# volume_board_v3.net
KiCad netlist of a schematic drawn in EAGLE
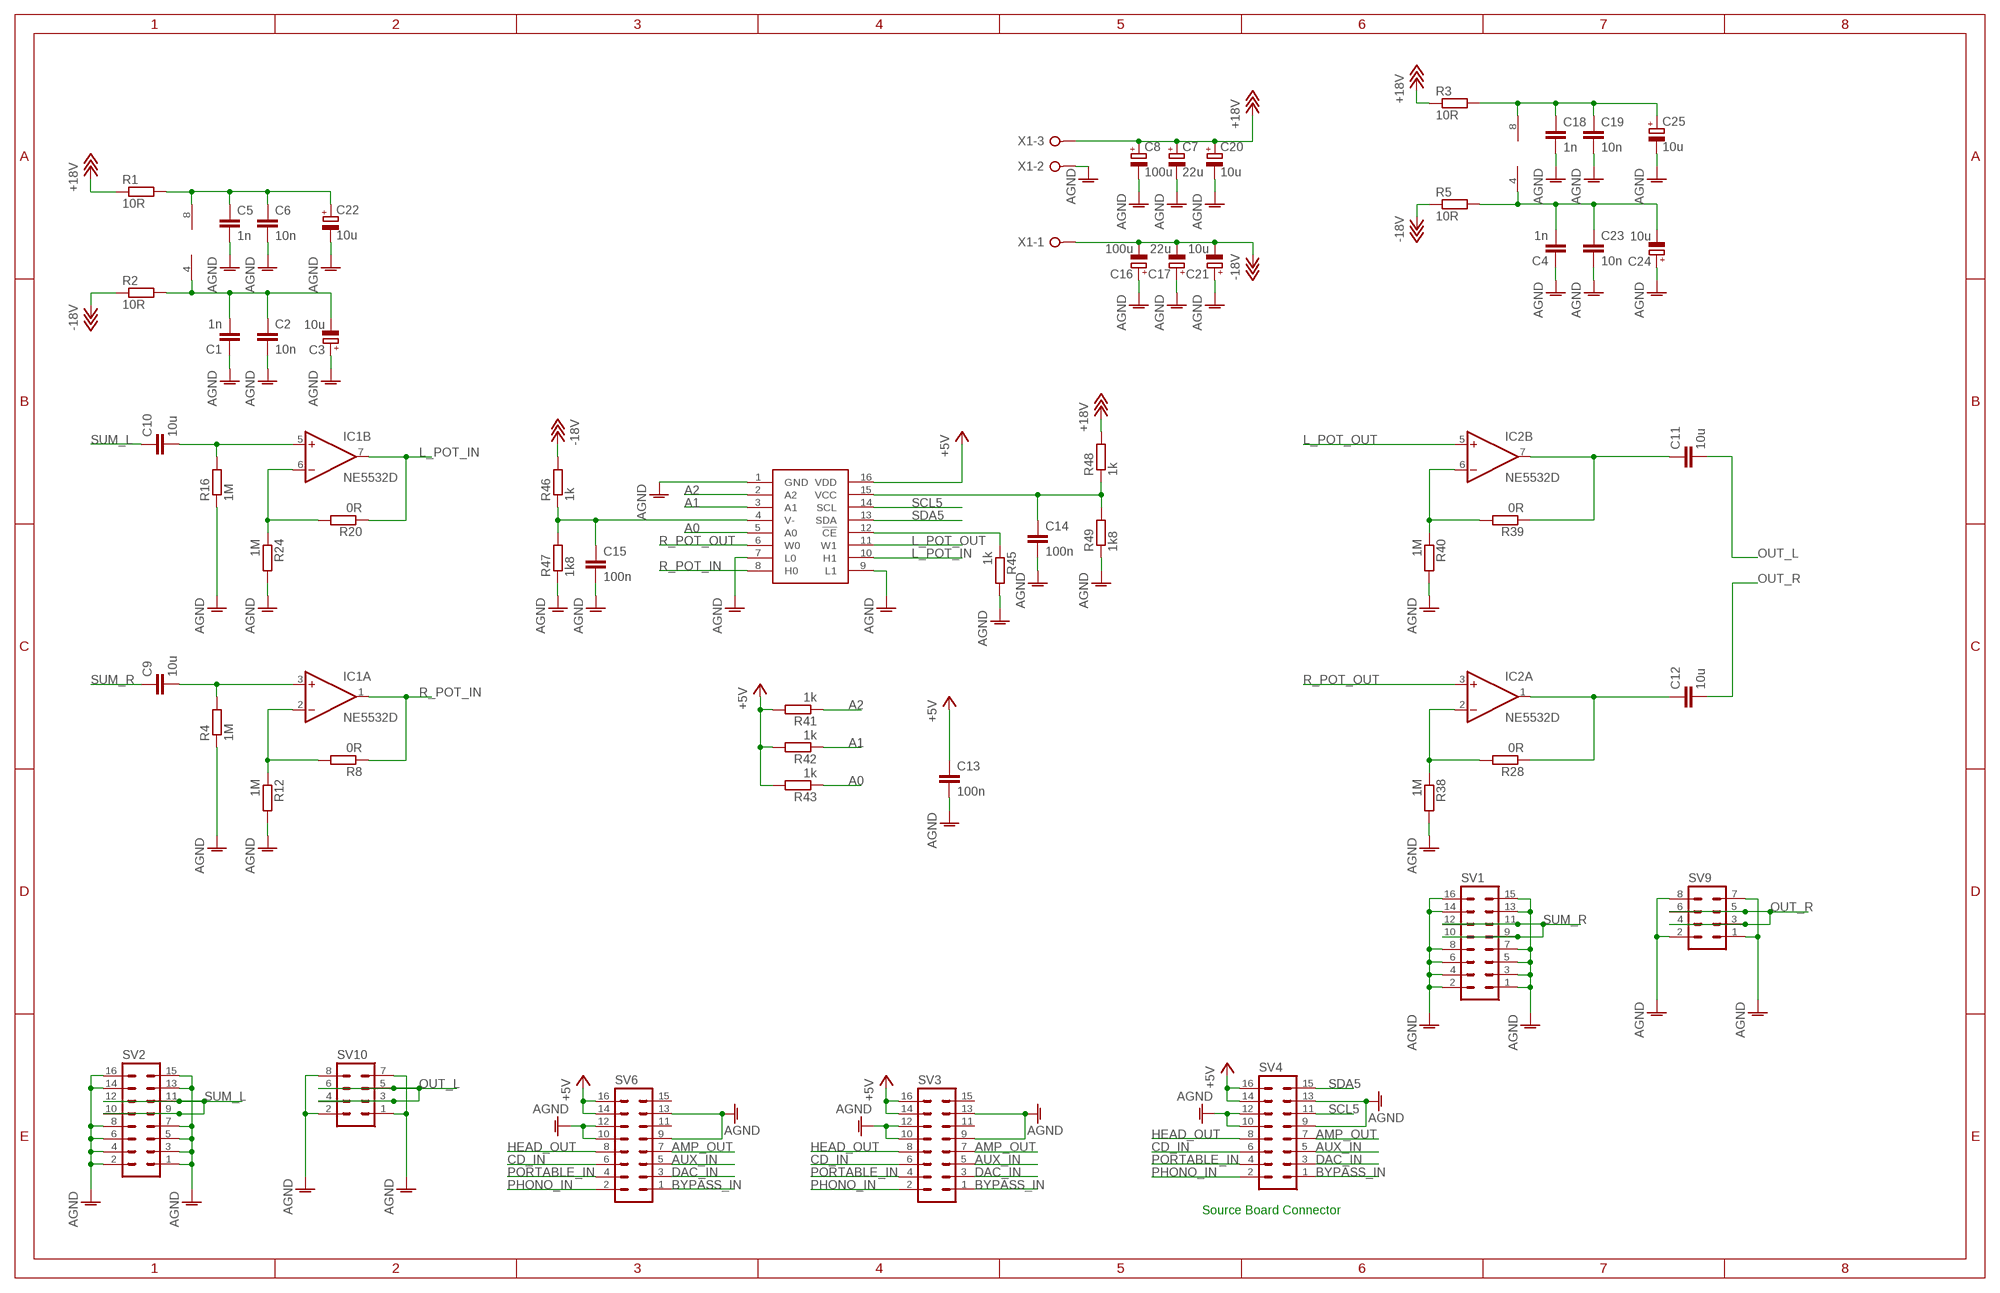
[diagram p0: schematic, sheet 1]

(export (version "E")
  (design (tool "Eeschema 10.0.6"))
  (components
    (comp (ref "C1")
      (value "1n")
      (footprint "eagle-import:C0603")
      (libsource (lib "eagle-import") (part "C-EUC0603"))
    )
    (comp (ref "C2")
      (value "10n")
      (footprint "eagle-import:C0603")
      (libsource (lib "eagle-import") (part "C-EUC0603"))
    )
    (comp (ref "C3")
      (value "10u")
      (footprint "eagle-import:153CLV-0405")
      (libsource (lib "eagle-import") (part "CPOL-EU153CLV-0405"))
    )
    (comp (ref "C4")
      (value "1n")
      (footprint "eagle-import:C0603")
      (libsource (lib "eagle-import") (part "C-EUC0603"))
    )
    (comp (ref "C5")
      (value "1n")
      (footprint "eagle-import:C0603")
      (libsource (lib "eagle-import") (part "C-EUC0603"))
    )
    (comp (ref "C6")
      (value "10n")
      (footprint "eagle-import:C0603")
      (libsource (lib "eagle-import") (part "C-EUC0603"))
    )
    (comp (ref "C7")
      (value "22u")
      (footprint "eagle-import:153CLV-0405")
      (libsource (lib "eagle-import") (part "CPOL-EU153CLV-0405"))
    )
    (comp (ref "C8")
      (value "100u")
      (footprint "eagle-import:153CLV-0605")
      (libsource (lib "eagle-import") (part "CPOL-EU153CLV-0605"))
    )
    (comp (ref "C9")
      (value "10u")
      (footprint "eagle-import:C5B7.2_11")
      (libsource (lib "eagle-import") (part "C5/7.2/11"))
    )
    (comp (ref "C10")
      (value "10u")
      (footprint "eagle-import:C5B7.2_11")
      (libsource (lib "eagle-import") (part "C5/7.2/11"))
    )
    (comp (ref "C11")
      (value "10u")
      (footprint "eagle-import:C5B7.2_11")
      (libsource (lib "eagle-import") (part "C5/7.2/11"))
    )
    (comp (ref "C12")
      (value "10u")
      (footprint "eagle-import:C5B7.2_11")
      (libsource (lib "eagle-import") (part "C5/7.2/11"))
    )
    (comp (ref "C13")
      (value "100n")
      (footprint "eagle-import:C0603")
      (libsource (lib "eagle-import") (part "C-EUC0603"))
    )
    (comp (ref "C14")
      (value "100n")
      (footprint "eagle-import:C0603")
      (libsource (lib "eagle-import") (part "C-EUC0603"))
    )
    (comp (ref "C15")
      (value "100n")
      (footprint "eagle-import:C0603")
      (libsource (lib "eagle-import") (part "C-EUC0603"))
    )
    (comp (ref "C16")
      (value "100u")
      (footprint "eagle-import:153CLV-0605")
      (libsource (lib "eagle-import") (part "CPOL-EU153CLV-0605"))
    )
    (comp (ref "C17")
      (value "22u")
      (footprint "eagle-import:153CLV-0405")
      (libsource (lib "eagle-import") (part "CPOL-EU153CLV-0405"))
    )
    (comp (ref "C18")
      (value "1n")
      (footprint "eagle-import:C0603")
      (libsource (lib "eagle-import") (part "C-EUC0603"))
    )
    (comp (ref "C19")
      (value "10n")
      (footprint "eagle-import:C0603")
      (libsource (lib "eagle-import") (part "C-EUC0603"))
    )
    (comp (ref "C20")
      (value "10u")
      (footprint "eagle-import:153CLV-0405")
      (libsource (lib "eagle-import") (part "CPOL-EU153CLV-0405"))
    )
    (comp (ref "C21")
      (value "10u")
      (footprint "eagle-import:153CLV-0405")
      (libsource (lib "eagle-import") (part "CPOL-EU153CLV-0405"))
    )
    (comp (ref "C22")
      (value "10u")
      (footprint "eagle-import:153CLV-0405")
      (libsource (lib "eagle-import") (part "CPOL-EU153CLV-0405"))
    )
    (comp (ref "C23")
      (value "10n")
      (footprint "eagle-import:C0603")
      (libsource (lib "eagle-import") (part "C-EUC0603"))
    )
    (comp (ref "C24")
      (value "10u")
      (footprint "eagle-import:153CLV-0405")
      (libsource (lib "eagle-import") (part "CPOL-EU153CLV-0405"))
    )
    (comp (ref "C25")
      (value "10u")
      (footprint "eagle-import:153CLV-0405")
      (libsource (lib "eagle-import") (part "CPOL-EU153CLV-0405"))
    )
    (comp (ref "IC1")
      (value "NE5532D")
      (footprint "eagle-import:SO08")
      (libsource (lib "eagle-import") (part "NE5532D"))
    )
    (comp (ref "IC2")
      (value "NE5532D")
      (footprint "eagle-import:SO08")
      (libsource (lib "eagle-import") (part "NE5532D"))
    )
    (comp (ref "IC4")
      (value "DS1882")
      (footprint "eagle-import:SO16")
      (libsource (lib "eagle-import") (part "DS1882"))
    )
    (comp (ref "R1")
      (value "10R")
      (footprint "eagle-import:R0603")
      (libsource (lib "eagle-import") (part "R-EU_R0603"))
    )
    (comp (ref "R2")
      (value "10R")
      (footprint "eagle-import:R0603")
      (libsource (lib "eagle-import") (part "R-EU_R0603"))
    )
    (comp (ref "R3")
      (value "10R")
      (footprint "eagle-import:R0603")
      (libsource (lib "eagle-import") (part "R-EU_R0603"))
    )
    (comp (ref "R4")
      (value "1M")
      (footprint "eagle-import:R0603")
      (libsource (lib "eagle-import") (part "resistor_R-EU_R0603"))
    )
    (comp (ref "R5")
      (value "10R")
      (footprint "eagle-import:R0603")
      (libsource (lib "eagle-import") (part "R-EU_R0603"))
    )
    (comp (ref "R8")
      (value "0R")
      (footprint "eagle-import:R0603")
      (libsource (lib "eagle-import") (part "resistor_R-EU_R0603"))
    )
    (comp (ref "R12")
      (value "1M")
      (footprint "eagle-import:R0603")
      (libsource (lib "eagle-import") (part "resistor_R-EU_R0603"))
    )
    (comp (ref "R16")
      (value "1M")
      (footprint "eagle-import:R0603")
      (libsource (lib "eagle-import") (part "resistor_R-EU_R0603"))
    )
    (comp (ref "R20")
      (value "0R")
      (footprint "eagle-import:R0603")
      (libsource (lib "eagle-import") (part "resistor_R-EU_R0603"))
    )
    (comp (ref "R24")
      (value "1M")
      (footprint "eagle-import:R0603")
      (libsource (lib "eagle-import") (part "resistor_R-EU_R0603"))
    )
    (comp (ref "R28")
      (value "0R")
      (footprint "eagle-import:R0603")
      (libsource (lib "eagle-import") (part "resistor_R-EU_R0603"))
    )
    (comp (ref "R38")
      (value "1M")
      (footprint "eagle-import:R0603")
      (libsource (lib "eagle-import") (part "resistor_R-EU_R0603"))
    )
    (comp (ref "R39")
      (value "0R")
      (footprint "eagle-import:R0603")
      (libsource (lib "eagle-import") (part "resistor_R-EU_R0603"))
    )
    (comp (ref "R40")
      (value "1M")
      (footprint "eagle-import:R0603")
      (libsource (lib "eagle-import") (part "resistor_R-EU_R0603"))
    )
    (comp (ref "R41")
      (value "1k")
      (footprint "eagle-import:R0603")
      (libsource (lib "eagle-import") (part "resistor_R-EU_R0603"))
    )
    (comp (ref "R42")
      (value "1k")
      (footprint "eagle-import:R0603")
      (libsource (lib "eagle-import") (part "resistor_R-EU_R0603"))
    )
    (comp (ref "R43")
      (value "1k")
      (footprint "eagle-import:R0603")
      (libsource (lib "eagle-import") (part "resistor_R-EU_R0603"))
    )
    (comp (ref "R45")
      (value "1k")
      (footprint "eagle-import:R0603")
      (libsource (lib "eagle-import") (part "resistor_R-EU_R0603"))
    )
    (comp (ref "R46")
      (value "1k")
      (footprint "eagle-import:R0603")
      (libsource (lib "eagle-import") (part "resistor_R-EU_R0603"))
    )
    (comp (ref "R47")
      (value "1k8")
      (footprint "eagle-import:R0603")
      (libsource (lib "eagle-import") (part "resistor_R-EU_R0603"))
    )
    (comp (ref "R48")
      (value "1k")
      (footprint "eagle-import:R0603")
      (libsource (lib "eagle-import") (part "resistor_R-EU_R0603"))
    )
    (comp (ref "R49")
      (value "1k8")
      (footprint "eagle-import:R0603")
      (libsource (lib "eagle-import") (part "resistor_R-EU_R0603"))
    )
    (comp (ref "SV1")
      (value "MA08-2")
      (footprint "eagle-import:MA08-2")
      (libsource (lib "eagle-import") (part "MA08-2"))
    )
    (comp (ref "SV2")
      (value "MA08-2")
      (footprint "eagle-import:MA08-2")
      (libsource (lib "eagle-import") (part "MA08-2"))
    )
    (comp (ref "SV3")
      (value "MA08-2")
      (footprint "eagle-import:MA08-2")
      (libsource (lib "eagle-import") (part "MA08-2"))
    )
    (comp (ref "SV4")
      (value "MA08-2B")
      (footprint "eagle-import:MA08-2_BORDER")
      (libsource (lib "eagle-import") (part "MA08-2B"))
    )
    (comp (ref "SV6")
      (value "MA08-2")
      (footprint "eagle-import:MA08-2")
      (libsource (lib "eagle-import") (part "MA08-2"))
    )
    (comp (ref "SV9")
      (value "MA04-2")
      (footprint "eagle-import:MA04-2")
      (libsource (lib "eagle-import") (part "MA04-2"))
    )
    (comp (ref "SV10")
      (value "MA04-2")
      (footprint "eagle-import:MA04-2")
      (libsource (lib "eagle-import") (part "MA04-2"))
    )
    (comp (ref "X1")
      (value "W237-3E")
      (footprint "eagle-import:W237-3E")
      (libsource (lib "eagle-import") (part "W237-3E"))
    )
  )
  (nets
    (net (code "1") (name "+5V") (class "Default")
      (node (ref "C13") (pin "1") (pinfunction "1_1") (pintype "passive"))
      (node (ref "IC4") (pin "16") (pinfunction "VDD_16") (pintype "power_in"))
      (node (ref "R41") (pin "2") (pinfunction "2_2") (pintype "passive"))
      (node (ref "R42") (pin "2") (pinfunction "2_2") (pintype "passive"))
      (node (ref "R43") (pin "2") (pinfunction "2_2") (pintype "passive"))
      (node (ref "SV3") (pin "14") (pinfunction "14_14") (pintype "passive"))
      (node (ref "SV3") (pin "16") (pinfunction "16_16") (pintype "passive"))
      (node (ref "SV4") (pin "14") (pinfunction "14_14") (pintype "passive"))
      (node (ref "SV4") (pin "16") (pinfunction "16_16") (pintype "passive"))
      (node (ref "SV6") (pin "14") (pinfunction "14_14") (pintype "passive"))
      (node (ref "SV6") (pin "16") (pinfunction "16_16") (pintype "passive"))
    )
    (net (code "2") (name "+18V") (class "Default")
      (node (ref "C20") (pin "+") (pinfunction "+_+") (pintype "passive"))
      (node (ref "C7") (pin "+") (pinfunction "+_+") (pintype "passive"))
      (node (ref "C8") (pin "+") (pinfunction "+_+") (pintype "passive"))
      (node (ref "R1") (pin "1") (pinfunction "1_1") (pintype "passive"))
      (node (ref "R3") (pin "1") (pinfunction "1_1") (pintype "passive"))
      (node (ref "R48") (pin "2") (pinfunction "2_2") (pintype "passive"))
      (node (ref "X1") (pin "3") (pinfunction "KL_3") (pintype "passive"))
    )
    (net (code "3") (name "-18V") (class "Default")
      (node (ref "C16") (pin "-") (pinfunction "-_-") (pintype "passive"))
      (node (ref "C17") (pin "-") (pinfunction "-_-") (pintype "passive"))
      (node (ref "C21") (pin "-") (pinfunction "-_-") (pintype "passive"))
      (node (ref "R2") (pin "1") (pinfunction "1_1") (pintype "passive"))
      (node (ref "R46") (pin "2") (pinfunction "2_2") (pintype "passive"))
      (node (ref "R5") (pin "1") (pinfunction "1_1") (pintype "passive"))
      (node (ref "X1") (pin "1") (pinfunction "KL_1") (pintype "passive"))
    )
    (net (code "4") (name "/A0") (class "Default")
      (node (ref "IC4") (pin "5") (pinfunction "A0_5") (pintype "bidirectional"))
      (node (ref "R43") (pin "1") (pinfunction "1_1") (pintype "passive"))
    )
    (net (code "5") (name "/A1") (class "Default")
      (node (ref "IC4") (pin "3") (pinfunction "A1_3") (pintype "bidirectional"))
      (node (ref "R42") (pin "1") (pinfunction "1_1") (pintype "passive"))
    )
    (net (code "6") (name "/A2") (class "Default")
      (node (ref "IC4") (pin "2") (pinfunction "A2_2") (pintype "bidirectional"))
      (node (ref "R41") (pin "1") (pinfunction "1_1") (pintype "passive"))
    )
    (net (code "7") (name "/AMP_OUT") (class "Default")
      (node (ref "SV3") (pin "7") (pinfunction "7_7") (pintype "passive"))
      (node (ref "SV4") (pin "7") (pinfunction "7_7") (pintype "passive"))
      (node (ref "SV6") (pin "7") (pinfunction "7_7") (pintype "passive"))
    )
    (net (code "8") (name "/AUX_IN") (class "Default")
      (node (ref "SV3") (pin "5") (pinfunction "5_5") (pintype "passive"))
      (node (ref "SV4") (pin "5") (pinfunction "5_5") (pintype "passive"))
      (node (ref "SV6") (pin "5") (pinfunction "5_5") (pintype "passive"))
    )
    (net (code "9") (name "/BYPASS_IN") (class "Default")
      (node (ref "SV3") (pin "1") (pinfunction "1_1") (pintype "passive"))
      (node (ref "SV4") (pin "1") (pinfunction "1_1") (pintype "passive"))
      (node (ref "SV6") (pin "1") (pinfunction "1_1") (pintype "passive"))
    )
    (net (code "10") (name "/CD_IN") (class "Default")
      (node (ref "SV3") (pin "6") (pinfunction "6_6") (pintype "passive"))
      (node (ref "SV4") (pin "6") (pinfunction "6_6") (pintype "passive"))
      (node (ref "SV6") (pin "6") (pinfunction "6_6") (pintype "passive"))
    )
    (net (code "11") (name "/DAC_IN") (class "Default")
      (node (ref "SV3") (pin "3") (pinfunction "3_3") (pintype "passive"))
      (node (ref "SV4") (pin "3") (pinfunction "3_3") (pintype "passive"))
      (node (ref "SV6") (pin "3") (pinfunction "3_3") (pintype "passive"))
    )
    (net (code "12") (name "/HEAD_OUT") (class "Default")
      (node (ref "SV3") (pin "8") (pinfunction "8_8") (pintype "passive"))
      (node (ref "SV4") (pin "8") (pinfunction "8_8") (pintype "passive"))
      (node (ref "SV6") (pin "8") (pinfunction "8_8") (pintype "passive"))
    )
    (net (code "13") (name "/L_POT_IN") (class "Default")
      (node (ref "IC1") (pin "7") (pinfunction "OUT_7") (pintype "output"))
      (node (ref "IC4") (pin "10") (pinfunction "H1_10") (pintype "bidirectional"))
      (node (ref "R20") (pin "1") (pinfunction "1_1") (pintype "passive"))
    )
    (net (code "14") (name "/L_POT_OUT") (class "Default")
      (node (ref "IC2") (pin "5") (pinfunction "+IN_5") (pintype "input"))
      (node (ref "IC4") (pin "11") (pinfunction "W1_11") (pintype "bidirectional"))
    )
    (net (code "15") (name "/OUT_L") (class "Default")
      (node (ref "C11") (pin "2") (pinfunction "2_2") (pintype "passive"))
      (node (ref "SV10") (pin "3") (pinfunction "3_3") (pintype "passive"))
      (node (ref "SV10") (pin "4") (pinfunction "4_4") (pintype "passive"))
      (node (ref "SV10") (pin "5") (pinfunction "5_5") (pintype "passive"))
      (node (ref "SV10") (pin "6") (pinfunction "6_6") (pintype "passive"))
    )
    (net (code "16") (name "/OUT_R") (class "Default")
      (node (ref "C12") (pin "2") (pinfunction "2_2") (pintype "passive"))
      (node (ref "SV9") (pin "3") (pinfunction "3_3") (pintype "passive"))
      (node (ref "SV9") (pin "4") (pinfunction "4_4") (pintype "passive"))
      (node (ref "SV9") (pin "5") (pinfunction "5_5") (pintype "passive"))
      (node (ref "SV9") (pin "6") (pinfunction "6_6") (pintype "passive"))
    )
    (net (code "17") (name "/PHONO_IN") (class "Default")
      (node (ref "SV3") (pin "2") (pinfunction "2_2") (pintype "passive"))
      (node (ref "SV4") (pin "2") (pinfunction "2_2") (pintype "passive"))
      (node (ref "SV6") (pin "2") (pinfunction "2_2") (pintype "passive"))
    )
    (net (code "18") (name "/PORTABLE_IN") (class "Default")
      (node (ref "SV3") (pin "4") (pinfunction "4_4") (pintype "passive"))
      (node (ref "SV4") (pin "4") (pinfunction "4_4") (pintype "passive"))
      (node (ref "SV6") (pin "4") (pinfunction "4_4") (pintype "passive"))
    )
    (net (code "19") (name "/R_POT_IN") (class "Default")
      (node (ref "IC1") (pin "1") (pinfunction "OUT_1") (pintype "output"))
      (node (ref "IC4") (pin "8") (pinfunction "H0_8") (pintype "bidirectional"))
      (node (ref "R8") (pin "1") (pinfunction "1_1") (pintype "passive"))
    )
    (net (code "20") (name "/R_POT_OUT") (class "Default")
      (node (ref "IC2") (pin "3") (pinfunction "+IN_3") (pintype "input"))
      (node (ref "IC4") (pin "6") (pinfunction "W0_6") (pintype "bidirectional"))
    )
    (net (code "21") (name "/SCL5") (class "Default")
      (node (ref "IC4") (pin "14") (pinfunction "SCL_14") (pintype "bidirectional"))
      (node (ref "SV4") (pin "11") (pinfunction "11_11") (pintype "passive"))
    )
    (net (code "22") (name "/SDA5") (class "Default")
      (node (ref "IC4") (pin "13") (pinfunction "SDA_13") (pintype "bidirectional"))
      (node (ref "SV4") (pin "15") (pinfunction "15_15") (pintype "passive"))
    )
    (net (code "23") (name "/SUM_L") (class "Default")
      (node (ref "C10") (pin "1") (pinfunction "1_1") (pintype "passive"))
      (node (ref "SV2") (pin "10") (pinfunction "10_10") (pintype "passive"))
      (node (ref "SV2") (pin "11") (pinfunction "11_11") (pintype "passive"))
      (node (ref "SV2") (pin "12") (pinfunction "12_12") (pintype "passive"))
      (node (ref "SV2") (pin "9") (pinfunction "9_9") (pintype "passive"))
    )
    (net (code "24") (name "/SUM_R") (class "Default")
      (node (ref "C9") (pin "1") (pinfunction "1_1") (pintype "passive"))
      (node (ref "SV1") (pin "10") (pinfunction "10_10") (pintype "passive"))
      (node (ref "SV1") (pin "11") (pinfunction "11_11") (pintype "passive"))
      (node (ref "SV1") (pin "12") (pinfunction "12_12") (pintype "passive"))
      (node (ref "SV1") (pin "9") (pinfunction "9_9") (pintype "passive"))
    )
    (net (code "25") (name "AGND") (class "Default")
      (node (ref "C1") (pin "1") (pinfunction "1_1") (pintype "passive"))
      (node (ref "C13") (pin "2") (pinfunction "2_2") (pintype "passive"))
      (node (ref "C14") (pin "2") (pinfunction "2_2") (pintype "passive"))
      (node (ref "C15") (pin "2") (pinfunction "2_2") (pintype "passive"))
      (node (ref "C16") (pin "+") (pinfunction "+_+") (pintype "passive"))
      (node (ref "C17") (pin "+") (pinfunction "+_+") (pintype "passive"))
      (node (ref "C18") (pin "2") (pinfunction "2_2") (pintype "passive"))
      (node (ref "C19") (pin "2") (pinfunction "2_2") (pintype "passive"))
      (node (ref "C2") (pin "2") (pinfunction "2_2") (pintype "passive"))
      (node (ref "C20") (pin "-") (pinfunction "-_-") (pintype "passive"))
      (node (ref "C21") (pin "+") (pinfunction "+_+") (pintype "passive"))
      (node (ref "C22") (pin "-") (pinfunction "-_-") (pintype "passive"))
      (node (ref "C23") (pin "2") (pinfunction "2_2") (pintype "passive"))
      (node (ref "C24") (pin "+") (pinfunction "+_+") (pintype "passive"))
      (node (ref "C25") (pin "-") (pinfunction "-_-") (pintype "passive"))
      (node (ref "C3") (pin "+") (pinfunction "+_+") (pintype "passive"))
      (node (ref "C4") (pin "1") (pinfunction "1_1") (pintype "passive"))
      (node (ref "C5") (pin "2") (pinfunction "2_2") (pintype "passive"))
      (node (ref "C6") (pin "2") (pinfunction "2_2") (pintype "passive"))
      (node (ref "C7") (pin "-") (pinfunction "-_-") (pintype "passive"))
      (node (ref "C8") (pin "-") (pinfunction "-_-") (pintype "passive"))
      (node (ref "IC4") (pin "1") (pinfunction "GND_1") (pintype "power_in"))
      (node (ref "IC4") (pin "7") (pinfunction "L0_7") (pintype "bidirectional"))
      (node (ref "IC4") (pin "9") (pinfunction "L1_9") (pintype "bidirectional"))
      (node (ref "R12") (pin "2") (pinfunction "2_2") (pintype "passive"))
      (node (ref "R16") (pin "1") (pinfunction "1_1") (pintype "passive"))
      (node (ref "R24") (pin "2") (pinfunction "2_2") (pintype "passive"))
      (node (ref "R38") (pin "2") (pinfunction "2_2") (pintype "passive"))
      (node (ref "R4") (pin "1") (pinfunction "1_1") (pintype "passive"))
      (node (ref "R40") (pin "2") (pinfunction "2_2") (pintype "passive"))
      (node (ref "R45") (pin "2") (pinfunction "2_2") (pintype "passive"))
      (node (ref "R47") (pin "1") (pinfunction "1_1") (pintype "passive"))
      (node (ref "R49") (pin "1") (pinfunction "1_1") (pintype "passive"))
      (node (ref "SV1") (pin "1") (pinfunction "1_1") (pintype "passive"))
      (node (ref "SV1") (pin "13") (pinfunction "13_13") (pintype "passive"))
      (node (ref "SV1") (pin "14") (pinfunction "14_14") (pintype "passive"))
      (node (ref "SV1") (pin "15") (pinfunction "15_15") (pintype "passive"))
      (node (ref "SV1") (pin "16") (pinfunction "16_16") (pintype "passive"))
      (node (ref "SV1") (pin "2") (pinfunction "2_2") (pintype "passive"))
      (node (ref "SV1") (pin "3") (pinfunction "3_3") (pintype "passive"))
      (node (ref "SV1") (pin "4") (pinfunction "4_4") (pintype "passive"))
      (node (ref "SV1") (pin "5") (pinfunction "5_5") (pintype "passive"))
      (node (ref "SV1") (pin "6") (pinfunction "6_6") (pintype "passive"))
      (node (ref "SV1") (pin "7") (pinfunction "7_7") (pintype "passive"))
      (node (ref "SV1") (pin "8") (pinfunction "8_8") (pintype "passive"))
      (node (ref "SV10") (pin "1") (pinfunction "1_1") (pintype "passive"))
      (node (ref "SV10") (pin "2") (pinfunction "2_2") (pintype "passive"))
      (node (ref "SV10") (pin "7") (pinfunction "7_7") (pintype "passive"))
      (node (ref "SV10") (pin "8") (pinfunction "8_8") (pintype "passive"))
      (node (ref "SV2") (pin "1") (pinfunction "1_1") (pintype "passive"))
      (node (ref "SV2") (pin "13") (pinfunction "13_13") (pintype "passive"))
      (node (ref "SV2") (pin "14") (pinfunction "14_14") (pintype "passive"))
      (node (ref "SV2") (pin "15") (pinfunction "15_15") (pintype "passive"))
      (node (ref "SV2") (pin "16") (pinfunction "16_16") (pintype "passive"))
      (node (ref "SV2") (pin "2") (pinfunction "2_2") (pintype "passive"))
      (node (ref "SV2") (pin "3") (pinfunction "3_3") (pintype "passive"))
      (node (ref "SV2") (pin "4") (pinfunction "4_4") (pintype "passive"))
      (node (ref "SV2") (pin "5") (pinfunction "5_5") (pintype "passive"))
      (node (ref "SV2") (pin "6") (pinfunction "6_6") (pintype "passive"))
      (node (ref "SV2") (pin "7") (pinfunction "7_7") (pintype "passive"))
      (node (ref "SV2") (pin "8") (pinfunction "8_8") (pintype "passive"))
      (node (ref "SV3") (pin "10") (pinfunction "10_10") (pintype "passive"))
      (node (ref "SV3") (pin "12") (pinfunction "12_12") (pintype "passive"))
      (node (ref "SV3") (pin "13") (pinfunction "13_13") (pintype "passive"))
      (node (ref "SV3") (pin "9") (pinfunction "9_9") (pintype "passive"))
      (node (ref "SV4") (pin "10") (pinfunction "10_10") (pintype "passive"))
      (node (ref "SV4") (pin "12") (pinfunction "12_12") (pintype "passive"))
      (node (ref "SV4") (pin "13") (pinfunction "13_13") (pintype "passive"))
      (node (ref "SV4") (pin "9") (pinfunction "9_9") (pintype "passive"))
      (node (ref "SV6") (pin "10") (pinfunction "10_10") (pintype "passive"))
      (node (ref "SV6") (pin "12") (pinfunction "12_12") (pintype "passive"))
      (node (ref "SV6") (pin "13") (pinfunction "13_13") (pintype "passive"))
      (node (ref "SV6") (pin "9") (pinfunction "9_9") (pintype "passive"))
      (node (ref "SV9") (pin "1") (pinfunction "1_1") (pintype "passive"))
      (node (ref "SV9") (pin "2") (pinfunction "2_2") (pintype "passive"))
      (node (ref "SV9") (pin "7") (pinfunction "7_7") (pintype "passive"))
      (node (ref "SV9") (pin "8") (pinfunction "8_8") (pintype "passive"))
      (node (ref "X1") (pin "2") (pinfunction "KL_2") (pintype "passive"))
    )
    (net (code "26") (name "Net-(IC1A-+IN)") (class "Default")
      (node (ref "C9") (pin "2") (pinfunction "2_2") (pintype "passive"))
      (node (ref "IC1") (pin "3") (pinfunction "+IN_3") (pintype "input"))
      (node (ref "R4") (pin "2") (pinfunction "2_2") (pintype "passive"))
    )
    (net (code "27") (name "Net-(IC1A--IN)") (class "Default")
      (node (ref "IC1") (pin "2") (pinfunction "-IN_2") (pintype "input"))
      (node (ref "R12") (pin "1") (pinfunction "1_1") (pintype "passive"))
      (node (ref "R8") (pin "2") (pinfunction "2_2") (pintype "passive"))
    )
    (net (code "28") (name "Net-(IC1B-+IN)") (class "Default")
      (node (ref "C10") (pin "2") (pinfunction "2_2") (pintype "passive"))
      (node (ref "IC1") (pin "5") (pinfunction "+IN_5") (pintype "input"))
      (node (ref "R16") (pin "2") (pinfunction "2_2") (pintype "passive"))
    )
    (net (code "29") (name "Net-(IC1B--IN)") (class "Default")
      (node (ref "IC1") (pin "6") (pinfunction "-IN_6") (pintype "input"))
      (node (ref "R20") (pin "2") (pinfunction "2_2") (pintype "passive"))
      (node (ref "R24") (pin "1") (pinfunction "1_1") (pintype "passive"))
    )
    (net (code "30") (name "Net-(IC1C-V+)") (class "Default")
      (node (ref "C22") (pin "+") (pinfunction "+_+") (pintype "passive"))
      (node (ref "C5") (pin "1") (pinfunction "1_1") (pintype "passive"))
      (node (ref "C6") (pin "1") (pinfunction "1_1") (pintype "passive"))
      (node (ref "IC1") (pin "8") (pinfunction "V+_8") (pintype "power_in"))
      (node (ref "R1") (pin "2") (pinfunction "2_2") (pintype "passive"))
    )
    (net (code "31") (name "Net-(IC1C-V-)") (class "Default")
      (node (ref "C1") (pin "2") (pinfunction "2_2") (pintype "passive"))
      (node (ref "C2") (pin "1") (pinfunction "1_1") (pintype "passive"))
      (node (ref "C3") (pin "-") (pinfunction "-_-") (pintype "passive"))
      (node (ref "IC1") (pin "4") (pinfunction "V-_4") (pintype "power_in"))
      (node (ref "R2") (pin "2") (pinfunction "2_2") (pintype "passive"))
    )
    (net (code "32") (name "Net-(IC2A--IN)") (class "Default")
      (node (ref "IC2") (pin "2") (pinfunction "-IN_2") (pintype "input"))
      (node (ref "R28") (pin "2") (pinfunction "2_2") (pintype "passive"))
      (node (ref "R38") (pin "1") (pinfunction "1_1") (pintype "passive"))
    )
    (net (code "33") (name "Net-(IC2A-OUT)") (class "Default")
      (node (ref "C12") (pin "1") (pinfunction "1_1") (pintype "passive"))
      (node (ref "IC2") (pin "1") (pinfunction "OUT_1") (pintype "output"))
      (node (ref "R28") (pin "1") (pinfunction "1_1") (pintype "passive"))
    )
    (net (code "34") (name "Net-(IC2B--IN)") (class "Default")
      (node (ref "IC2") (pin "6") (pinfunction "-IN_6") (pintype "input"))
      (node (ref "R39") (pin "2") (pinfunction "2_2") (pintype "passive"))
      (node (ref "R40") (pin "1") (pinfunction "1_1") (pintype "passive"))
    )
    (net (code "35") (name "Net-(IC2B-OUT)") (class "Default")
      (node (ref "C11") (pin "1") (pinfunction "1_1") (pintype "passive"))
      (node (ref "IC2") (pin "7") (pinfunction "OUT_7") (pintype "output"))
      (node (ref "R39") (pin "1") (pinfunction "1_1") (pintype "passive"))
    )
    (net (code "36") (name "Net-(IC2C-V+)") (class "Default")
      (node (ref "C18") (pin "1") (pinfunction "1_1") (pintype "passive"))
      (node (ref "C19") (pin "1") (pinfunction "1_1") (pintype "passive"))
      (node (ref "C25") (pin "+") (pinfunction "+_+") (pintype "passive"))
      (node (ref "IC2") (pin "8") (pinfunction "V+_8") (pintype "power_in"))
      (node (ref "R3") (pin "2") (pinfunction "2_2") (pintype "passive"))
    )
    (net (code "37") (name "Net-(IC2C-V-)") (class "Default")
      (node (ref "C23") (pin "1") (pinfunction "1_1") (pintype "passive"))
      (node (ref "C24") (pin "-") (pinfunction "-_-") (pintype "passive"))
      (node (ref "C4") (pin "2") (pinfunction "2_2") (pintype "passive"))
      (node (ref "IC2") (pin "4") (pinfunction "V-_4") (pintype "power_in"))
      (node (ref "R5") (pin "2") (pinfunction "2_2") (pintype "passive"))
    )
    (net (code "38") (name "Net-(IC4-V-)") (class "Default")
      (node (ref "C15") (pin "1") (pinfunction "1_1") (pintype "passive"))
      (node (ref "IC4") (pin "4") (pinfunction "V-_4") (pintype "power_in"))
      (node (ref "R46") (pin "1") (pinfunction "1_1") (pintype "passive"))
      (node (ref "R47") (pin "2") (pinfunction "2_2") (pintype "passive"))
    )
    (net (code "39") (name "Net-(IC4-VCC)") (class "Default")
      (node (ref "C14") (pin "1") (pinfunction "1_1") (pintype "passive"))
      (node (ref "IC4") (pin "15") (pinfunction "VCC_15") (pintype "power_in"))
      (node (ref "R48") (pin "1") (pinfunction "1_1") (pintype "passive"))
      (node (ref "R49") (pin "2") (pinfunction "2_2") (pintype "passive"))
    )
    (net (code "40") (name "Net-(IC4-~{CE})") (class "Default")
      (node (ref "IC4") (pin "12") (pinfunction "~{CE}_12") (pintype "bidirectional"))
      (node (ref "R45") (pin "1") (pinfunction "1_1") (pintype "passive"))
    )
    (net (code "41") (name "unconnected-(SV3-Pad11)") (class "Default")
      (node (ref "SV3") (pin "11") (pinfunction "11_11") (pintype "passive"))
    )
    (net (code "42") (name "unconnected-(SV3-Pad15)") (class "Default")
      (node (ref "SV3") (pin "15") (pinfunction "15_15") (pintype "passive"))
    )
    (net (code "43") (name "unconnected-(SV6-Pad11)") (class "Default")
      (node (ref "SV6") (pin "11") (pinfunction "11_11") (pintype "passive"))
    )
    (net (code "44") (name "unconnected-(SV6-Pad15)") (class "Default")
      (node (ref "SV6") (pin "15") (pinfunction "15_15") (pintype "passive"))
    )
  )
)
